# LEDBoard.net
KiCad netlist of a schematic drawn in EAGLE
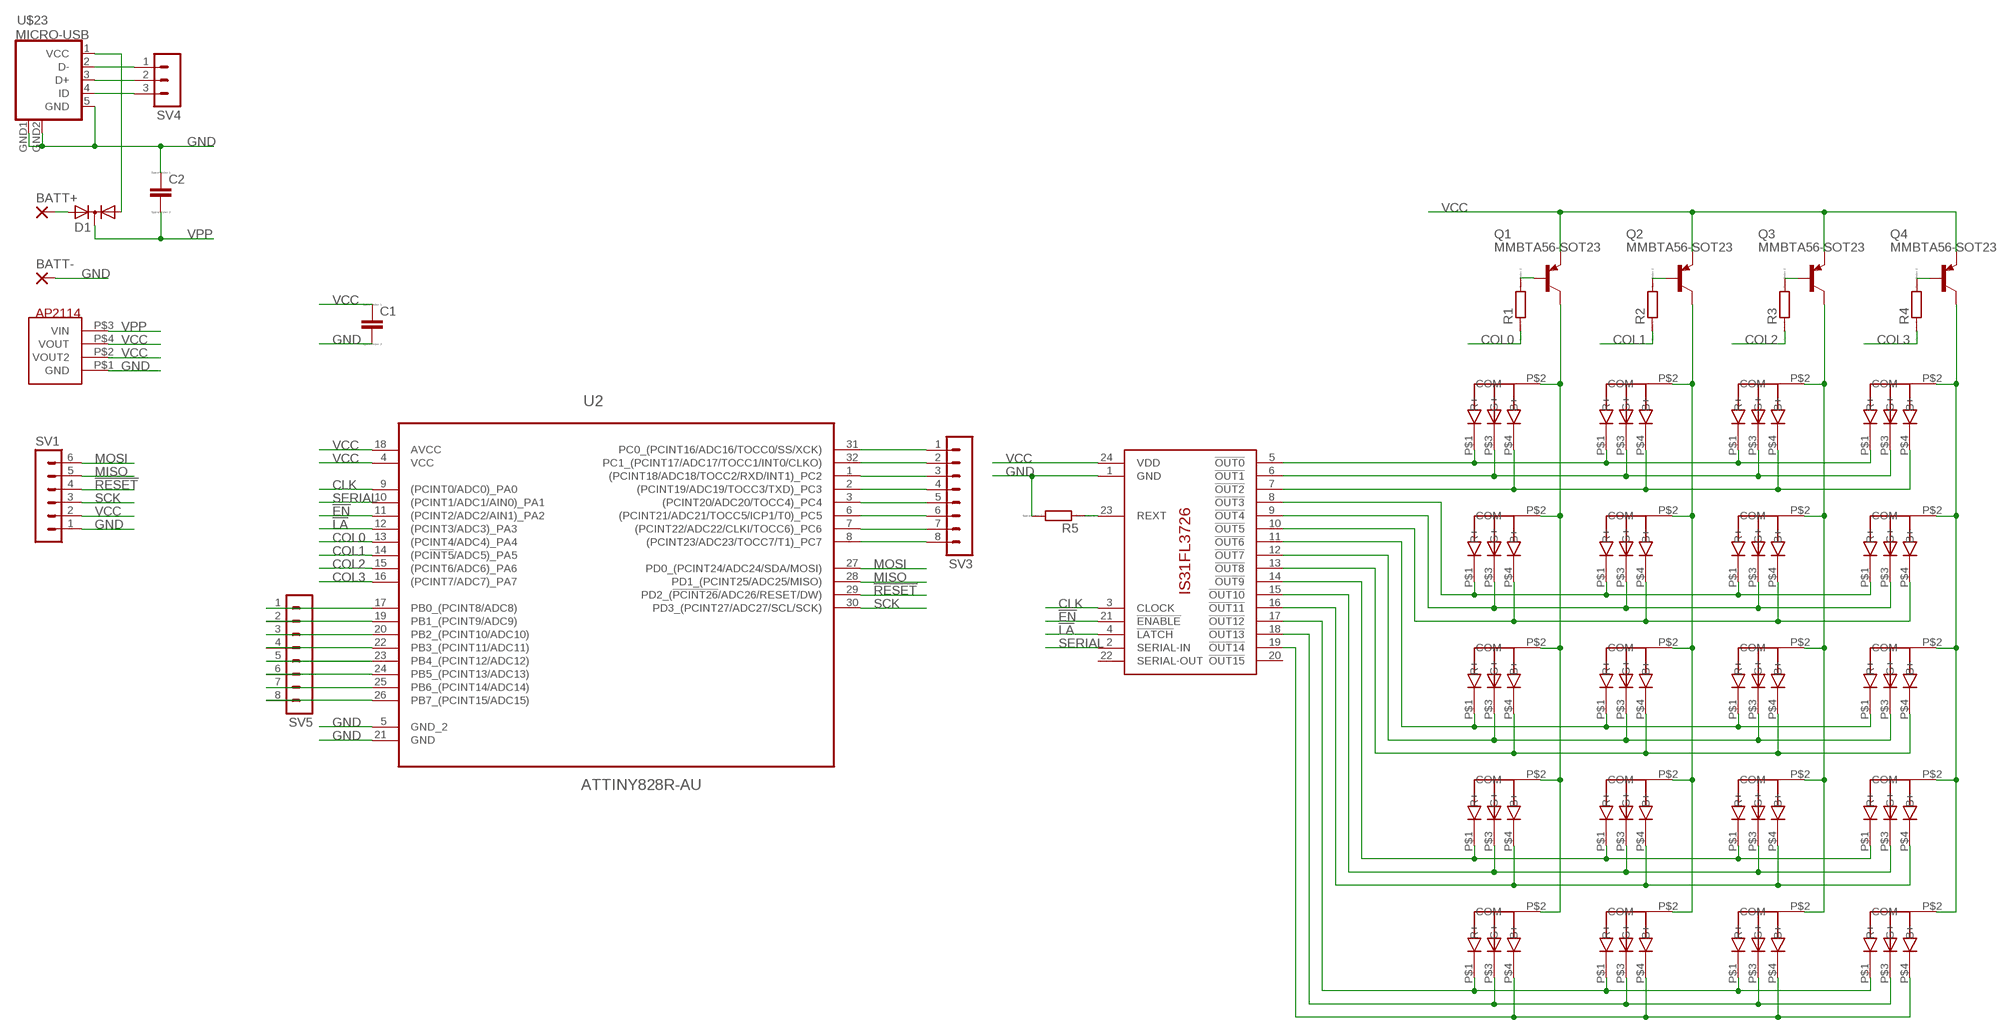
[diagram p0: schematic, sheet 1]

(export (version "E")
  (design (tool "Eeschema 10.0.6"))
  (components
    (comp (ref "BATT+")
      (value "2,54/1,1")
      (footprint "eagle-import:2,54_1,1")
      (libsource (lib "eagle-import") (part "2,54/1,1"))
    )
    (comp (ref "BATT-")
      (value "2,54/1,1")
      (footprint "eagle-import:2,54_1,1")
      (libsource (lib "eagle-import") (part "2,54/1,1"))
    )
    (comp (ref "C1")
      (value "CC1206")
      (footprint "eagle-import:C1206")
      (libsource (lib "eagle-import") (part "CC1206"))
    )
    (comp (ref "C2")
      (value "CC1206")
      (footprint "eagle-import:C1206")
      (libsource (lib "eagle-import") (part "CC1206"))
    )
    (comp (ref "D1")
      (value "DIODE-2AC|CASOT23")
      (footprint "eagle-import:SOT23")
      (libsource (lib "eagle-import") (part "DIODE-2AC|CASOT23"))
    )
    (comp (ref "Q1")
      (value "MMBTA56-SOT23")
      (footprint "eagle-import:SOT23")
      (libsource (lib "eagle-import") (part "-?SOT23MMBTA56"))
    )
    (comp (ref "Q2")
      (value "MMBTA56-SOT23")
      (footprint "eagle-import:SOT23")
      (libsource (lib "eagle-import") (part "-?SOT23MMBTA56"))
    )
    (comp (ref "Q3")
      (value "MMBTA56-SOT23")
      (footprint "eagle-import:SOT23")
      (libsource (lib "eagle-import") (part "-?SOT23MMBTA56"))
    )
    (comp (ref "Q4")
      (value "MMBTA56-SOT23")
      (footprint "eagle-import:SOT23")
      (libsource (lib "eagle-import") (part "-?SOT23MMBTA56"))
    )
    (comp (ref "R1")
      (value "RR1206")
      (footprint "eagle-import:R1206")
      (libsource (lib "eagle-import") (part "RR1206"))
    )
    (comp (ref "R2")
      (value "RR1206")
      (footprint "eagle-import:R1206")
      (libsource (lib "eagle-import") (part "RR1206"))
    )
    (comp (ref "R3")
      (value "RR1206")
      (footprint "eagle-import:R1206")
      (libsource (lib "eagle-import") (part "RR1206"))
    )
    (comp (ref "R4")
      (value "RR1206")
      (footprint "eagle-import:R1206")
      (libsource (lib "eagle-import") (part "RR1206"))
    )
    (comp (ref "R5")
      (value "RR1206")
      (footprint "eagle-import:R1206")
      (libsource (lib "eagle-import") (part "RR1206"))
    )
    (comp (ref "SV1")
      (value "MA06-1")
      (footprint "eagle-import:MA06-1")
      (libsource (lib "eagle-import") (part "MA06-1"))
    )
    (comp (ref "SV3")
      (value "MA08-1")
      (footprint "eagle-import:MA08-1")
      (libsource (lib "eagle-import") (part "MA08-1"))
    )
    (comp (ref "SV4")
      (value "MA03-1")
      (footprint "eagle-import:MA03-1")
      (libsource (lib "eagle-import") (part "MA03-1"))
    )
    (comp (ref "SV5")
      (value "MA08-1")
      (footprint "eagle-import:MA08-1")
      (libsource (lib "eagle-import") (part "MA08-1"))
    )
    (comp (ref "U$1")
      (value "IS31FL3726")
      (footprint "eagle-import:TSSOP-24")
      (libsource (lib "eagle-import") (part "IS31FL3726"))
    )
    (comp (ref "U$2")
      (value "AP2114H")
      (footprint "eagle-import:SOT233")
      (libsource (lib "eagle-import") (part "AP2114H"))
    )
    (comp (ref "U$3")
      (value "3528LED")
      (footprint "eagle-import:3528")
      (libsource (lib "eagle-import") (part "3528LED"))
    )
    (comp (ref "U$4")
      (value "3528LED")
      (footprint "eagle-import:3528")
      (libsource (lib "eagle-import") (part "3528LED"))
    )
    (comp (ref "U$5")
      (value "3528LED")
      (footprint "eagle-import:3528")
      (libsource (lib "eagle-import") (part "3528LED"))
    )
    (comp (ref "U$6")
      (value "3528LED")
      (footprint "eagle-import:3528")
      (libsource (lib "eagle-import") (part "3528LED"))
    )
    (comp (ref "U$7")
      (value "3528LED")
      (footprint "eagle-import:3528")
      (libsource (lib "eagle-import") (part "3528LED"))
    )
    (comp (ref "U$8")
      (value "3528LED")
      (footprint "eagle-import:3528")
      (libsource (lib "eagle-import") (part "3528LED"))
    )
    (comp (ref "U$9")
      (value "3528LED")
      (footprint "eagle-import:3528")
      (libsource (lib "eagle-import") (part "3528LED"))
    )
    (comp (ref "U$10")
      (value "3528LED")
      (footprint "eagle-import:3528")
      (libsource (lib "eagle-import") (part "3528LED"))
    )
    (comp (ref "U$11")
      (value "3528LED")
      (footprint "eagle-import:3528")
      (libsource (lib "eagle-import") (part "3528LED"))
    )
    (comp (ref "U$12")
      (value "3528LED")
      (footprint "eagle-import:3528")
      (libsource (lib "eagle-import") (part "3528LED"))
    )
    (comp (ref "U$13")
      (value "3528LED")
      (footprint "eagle-import:3528")
      (libsource (lib "eagle-import") (part "3528LED"))
    )
    (comp (ref "U$14")
      (value "3528LED")
      (footprint "eagle-import:3528")
      (libsource (lib "eagle-import") (part "3528LED"))
    )
    (comp (ref "U$15")
      (value "3528LED")
      (footprint "eagle-import:3528")
      (libsource (lib "eagle-import") (part "3528LED"))
    )
    (comp (ref "U$16")
      (value "3528LED")
      (footprint "eagle-import:3528")
      (libsource (lib "eagle-import") (part "3528LED"))
    )
    (comp (ref "U$17")
      (value "3528LED")
      (footprint "eagle-import:3528")
      (libsource (lib "eagle-import") (part "3528LED"))
    )
    (comp (ref "U$18")
      (value "3528LED")
      (footprint "eagle-import:3528")
      (libsource (lib "eagle-import") (part "3528LED"))
    )
    (comp (ref "U$19")
      (value "3528LED")
      (footprint "eagle-import:3528")
      (libsource (lib "eagle-import") (part "3528LED"))
    )
    (comp (ref "U$20")
      (value "3528LED")
      (footprint "eagle-import:3528")
      (libsource (lib "eagle-import") (part "3528LED"))
    )
    (comp (ref "U$21")
      (value "3528LED")
      (footprint "eagle-import:3528")
      (libsource (lib "eagle-import") (part "3528LED"))
    )
    (comp (ref "U$22")
      (value "3528LED")
      (footprint "eagle-import:3528")
      (libsource (lib "eagle-import") (part "3528LED"))
    )
    (comp (ref "U$23")
      (value "MICRO-USB")
      (footprint "eagle-import:MICRO-USB")
      (libsource (lib "eagle-import") (part "MICRO-USB"))
    )
    (comp (ref "U2")
      (value "ATTINY828R-AU")
      (footprint "eagle-import:QFP80P900X900X120-32N")
      (libsource (lib "eagle-import") (part "ATTINY828R-AU"))
    )
  )
  (nets
    (net (code "1") (name "/CLK") (class "Default")
      (node (ref "U$1") (pin "3") (pinfunction "CLOCK_3") (pintype "bidirectional"))
      (node (ref "U2") (pin "9") (pinfunction "(PCINT0/ADC0)_PA0_9") (pintype "bidirectional"))
    )
    (net (code "2") (name "/COL0") (class "Default")
      (node (ref "R1") (pin "1") (pinfunction "1_1") (pintype "passive"))
      (node (ref "U2") (pin "13") (pinfunction "(PCINT4/ADC4)_PA4_13") (pintype "bidirectional"))
    )
    (net (code "3") (name "/COL1") (class "Default")
      (node (ref "R2") (pin "1") (pinfunction "1_1") (pintype "passive"))
      (node (ref "U2") (pin "14") (pinfunction "(PC~{INT5}/ADC5)_PA5_14") (pintype "bidirectional"))
    )
    (net (code "4") (name "/COL2") (class "Default")
      (node (ref "R3") (pin "1") (pinfunction "1_1") (pintype "passive"))
      (node (ref "U2") (pin "15") (pinfunction "(PCINT6/ADC6)_PA6_15") (pintype "bidirectional"))
    )
    (net (code "5") (name "/COL3") (class "Default")
      (node (ref "R4") (pin "1") (pinfunction "1_1") (pintype "passive"))
      (node (ref "U2") (pin "16") (pinfunction "(PCINT7/ADC7)_PA7_16") (pintype "bidirectional"))
    )
    (net (code "6") (name "/GND") (class "Default")
      (node (ref "BATT-") (pin "1") (pinfunction "P_1") (pintype "passive"))
      (node (ref "C1") (pin "2") (pinfunction "2_2") (pintype "passive"))
      (node (ref "C2") (pin "1") (pinfunction "1_1") (pintype "passive"))
      (node (ref "R5") (pin "2") (pinfunction "2_2") (pintype "passive"))
      (node (ref "SV1") (pin "1") (pinfunction "1_1") (pintype "passive"))
      (node (ref "U$1") (pin "1") (pinfunction "GND_1") (pintype "bidirectional"))
      (node (ref "U$2") (pin "P$1") (pinfunction "GND_P$1") (pintype "bidirectional"))
      (node (ref "U$23") (pin "5") (pinfunction "GND_5") (pintype "power_in"))
      (node (ref "U$23") (pin "GND1") (pinfunction "GND_GND1") (pintype "power_in"))
      (node (ref "U$23") (pin "GND2") (pinfunction "GND_GND2") (pintype "power_in"))
      (node (ref "U2") (pin "21") (pinfunction "GND_21") (pintype "passive"))
      (node (ref "U2") (pin "5") (pinfunction "GND_2_5") (pintype "passive"))
    )
    (net (code "7") (name "/MISO") (class "Default")
      (node (ref "SV1") (pin "5") (pinfunction "5_5") (pintype "passive"))
      (node (ref "U2") (pin "28") (pinfunction "PD1_(PCINT25/ADC25/MISO)_28") (pintype "bidirectional"))
    )
    (net (code "8") (name "/MOSI") (class "Default")
      (node (ref "SV1") (pin "6") (pinfunction "6_6") (pintype "passive"))
      (node (ref "U2") (pin "27") (pinfunction "PD0_(PCINT24/ADC24/SDA/MOSI)_27") (pintype "bidirectional"))
    )
    (net (code "9") (name "/SCK") (class "Default")
      (node (ref "SV1") (pin "3") (pinfunction "3_3") (pintype "passive"))
      (node (ref "U2") (pin "30") (pinfunction "PD3_(PCINT27/ADC27/SCL/SCK)_30") (pintype "bidirectional"))
    )
    (net (code "10") (name "/SERIAL") (class "Default")
      (node (ref "U$1") (pin "2") (pinfunction "SERIAL-IN_2") (pintype "bidirectional"))
      (node (ref "U2") (pin "10") (pinfunction "(PCINT1/ADC1/AIN0)_PA1_10") (pintype "bidirectional"))
    )
    (net (code "11") (name "/VCC") (class "Default")
      (node (ref "C1") (pin "1") (pinfunction "1_1") (pintype "passive"))
      (node (ref "Q1") (pin "2") (pinfunction "E_2") (pintype "passive"))
      (node (ref "Q2") (pin "2") (pinfunction "E_2") (pintype "passive"))
      (node (ref "Q3") (pin "2") (pinfunction "E_2") (pintype "passive"))
      (node (ref "Q4") (pin "2") (pinfunction "E_2") (pintype "passive"))
      (node (ref "SV1") (pin "2") (pinfunction "2_2") (pintype "passive"))
      (node (ref "U$1") (pin "24") (pinfunction "VDD_24") (pintype "bidirectional"))
      (node (ref "U$2") (pin "P$2") (pinfunction "VOUT2_P$2") (pintype "bidirectional"))
      (node (ref "U$2") (pin "P$4") (pinfunction "VOUT_P$4") (pintype "bidirectional"))
      (node (ref "U2") (pin "18") (pinfunction "AVCC_18") (pintype "power_in"))
      (node (ref "U2") (pin "4") (pinfunction "VCC_4") (pintype "power_in"))
    )
    (net (code "12") (name "/VPP") (class "Default")
      (node (ref "C2") (pin "2") (pinfunction "2_2") (pintype "passive"))
      (node (ref "D1") (pin "3") (pinfunction "C_3") (pintype "passive"))
      (node (ref "U$2") (pin "P$3") (pinfunction "VIN_P$3") (pintype "bidirectional"))
    )
    (net (code "13") (name "/~{EN}") (class "Default")
      (node (ref "U$1") (pin "21") (pinfunction "~{ENABLE}_21") (pintype "bidirectional"))
      (node (ref "U2") (pin "11") (pinfunction "(PCINT2/ADC2/AIN1)_PA2_11") (pintype "bidirectional"))
    )
    (net (code "14") (name "/~{LA}") (class "Default")
      (node (ref "U$1") (pin "4") (pinfunction "~{LATCH}_4") (pintype "bidirectional"))
      (node (ref "U2") (pin "12") (pinfunction "(PCINT3/ADC3)_PA3_12") (pintype "bidirectional"))
    )
    (net (code "15") (name "/~{RESET}") (class "Default")
      (node (ref "SV1") (pin "4") (pinfunction "4_4") (pintype "passive"))
      (node (ref "U2") (pin "29") (pinfunction "PD2_(~{PCINT26}/ADC26/RESET/DW)_29") (pintype "bidirectional"))
    )
    (net (code "16") (name "Net-(BATT+-P)") (class "Default")
      (node (ref "BATT+") (pin "1") (pinfunction "P_1") (pintype "passive"))
      (node (ref "D1") (pin "2") (pinfunction "A2_2") (pintype "passive"))
    )
    (net (code "17") (name "Net-(D1-A1)") (class "Default")
      (node (ref "D1") (pin "1") (pinfunction "A1_1") (pintype "passive"))
      (node (ref "U$23") (pin "1") (pinfunction "VCC_1") (pintype "power_in"))
    )
    (net (code "18") (name "Net-(Q1-B)") (class "Default")
      (node (ref "Q1") (pin "1") (pinfunction "B_1") (pintype "passive"))
      (node (ref "R1") (pin "2") (pinfunction "2_2") (pintype "passive"))
    )
    (net (code "19") (name "Net-(Q1-C)") (class "Default")
      (node (ref "Q1") (pin "3") (pinfunction "C_3") (pintype "passive"))
      (node (ref "U$11") (pin "P$2") (pinfunction "COM_P$2") (pintype "bidirectional"))
      (node (ref "U$15") (pin "P$2") (pinfunction "COM_P$2") (pintype "bidirectional"))
      (node (ref "U$22") (pin "P$2") (pinfunction "COM_P$2") (pintype "bidirectional"))
      (node (ref "U$3") (pin "P$2") (pinfunction "COM_P$2") (pintype "bidirectional"))
      (node (ref "U$7") (pin "P$2") (pinfunction "COM_P$2") (pintype "bidirectional"))
    )
    (net (code "20") (name "Net-(Q2-B)") (class "Default")
      (node (ref "Q2") (pin "1") (pinfunction "B_1") (pintype "passive"))
      (node (ref "R2") (pin "2") (pinfunction "2_2") (pintype "passive"))
    )
    (net (code "21") (name "Net-(Q2-C)") (class "Default")
      (node (ref "Q2") (pin "3") (pinfunction "C_3") (pintype "passive"))
      (node (ref "U$12") (pin "P$2") (pinfunction "COM_P$2") (pintype "bidirectional"))
      (node (ref "U$16") (pin "P$2") (pinfunction "COM_P$2") (pintype "bidirectional"))
      (node (ref "U$21") (pin "P$2") (pinfunction "COM_P$2") (pintype "bidirectional"))
      (node (ref "U$4") (pin "P$2") (pinfunction "COM_P$2") (pintype "bidirectional"))
      (node (ref "U$8") (pin "P$2") (pinfunction "COM_P$2") (pintype "bidirectional"))
    )
    (net (code "22") (name "Net-(Q3-B)") (class "Default")
      (node (ref "Q3") (pin "1") (pinfunction "B_1") (pintype "passive"))
      (node (ref "R3") (pin "2") (pinfunction "2_2") (pintype "passive"))
    )
    (net (code "23") (name "Net-(Q3-C)") (class "Default")
      (node (ref "Q3") (pin "3") (pinfunction "C_3") (pintype "passive"))
      (node (ref "U$13") (pin "P$2") (pinfunction "COM_P$2") (pintype "bidirectional"))
      (node (ref "U$17") (pin "P$2") (pinfunction "COM_P$2") (pintype "bidirectional"))
      (node (ref "U$20") (pin "P$2") (pinfunction "COM_P$2") (pintype "bidirectional"))
      (node (ref "U$5") (pin "P$2") (pinfunction "COM_P$2") (pintype "bidirectional"))
      (node (ref "U$9") (pin "P$2") (pinfunction "COM_P$2") (pintype "bidirectional"))
    )
    (net (code "24") (name "Net-(Q4-B)") (class "Default")
      (node (ref "Q4") (pin "1") (pinfunction "B_1") (pintype "passive"))
      (node (ref "R4") (pin "2") (pinfunction "2_2") (pintype "passive"))
    )
    (net (code "25") (name "Net-(Q4-C)") (class "Default")
      (node (ref "Q4") (pin "3") (pinfunction "C_3") (pintype "passive"))
      (node (ref "U$10") (pin "P$2") (pinfunction "COM_P$2") (pintype "bidirectional"))
      (node (ref "U$14") (pin "P$2") (pinfunction "COM_P$2") (pintype "bidirectional"))
      (node (ref "U$18") (pin "P$2") (pinfunction "COM_P$2") (pintype "bidirectional"))
      (node (ref "U$19") (pin "P$2") (pinfunction "COM_P$2") (pintype "bidirectional"))
      (node (ref "U$6") (pin "P$2") (pinfunction "COM_P$2") (pintype "bidirectional"))
    )
    (net (code "26") (name "Net-(U$1-REXT)") (class "Default")
      (node (ref "R5") (pin "1") (pinfunction "1_1") (pintype "passive"))
      (node (ref "U$1") (pin "23") (pinfunction "REXT_23") (pintype "bidirectional"))
    )
    (net (code "27") (name "Net-(U$1-~{OUT0})") (class "Default")
      (node (ref "U$1") (pin "5") (pinfunction "~{OUT0}_5") (pintype "bidirectional"))
      (node (ref "U$10") (pin "P$1") (pinfunction "R+_P$1") (pintype "bidirectional"))
      (node (ref "U$7") (pin "P$1") (pinfunction "R+_P$1") (pintype "bidirectional"))
      (node (ref "U$8") (pin "P$1") (pinfunction "R+_P$1") (pintype "bidirectional"))
      (node (ref "U$9") (pin "P$1") (pinfunction "R+_P$1") (pintype "bidirectional"))
    )
    (net (code "28") (name "Net-(U$1-~{OUT1})") (class "Default")
      (node (ref "U$1") (pin "6") (pinfunction "~{OUT1}_6") (pintype "bidirectional"))
      (node (ref "U$10") (pin "P$3") (pinfunction "G+_P$3") (pintype "bidirectional"))
      (node (ref "U$7") (pin "P$3") (pinfunction "G+_P$3") (pintype "bidirectional"))
      (node (ref "U$8") (pin "P$3") (pinfunction "G+_P$3") (pintype "bidirectional"))
      (node (ref "U$9") (pin "P$3") (pinfunction "G+_P$3") (pintype "bidirectional"))
    )
    (net (code "29") (name "Net-(U$1-~{OUT2})") (class "Default")
      (node (ref "U$1") (pin "7") (pinfunction "~{OUT2}_7") (pintype "bidirectional"))
      (node (ref "U$10") (pin "P$4") (pinfunction "B+_P$4") (pintype "bidirectional"))
      (node (ref "U$7") (pin "P$4") (pinfunction "B+_P$4") (pintype "bidirectional"))
      (node (ref "U$8") (pin "P$4") (pinfunction "B+_P$4") (pintype "bidirectional"))
      (node (ref "U$9") (pin "P$4") (pinfunction "B+_P$4") (pintype "bidirectional"))
    )
    (net (code "30") (name "Net-(U$1-~{OUT3})") (class "Default")
      (node (ref "U$1") (pin "8") (pinfunction "~{OUT3}_8") (pintype "bidirectional"))
      (node (ref "U$3") (pin "P$1") (pinfunction "R+_P$1") (pintype "bidirectional"))
      (node (ref "U$4") (pin "P$1") (pinfunction "R+_P$1") (pintype "bidirectional"))
      (node (ref "U$5") (pin "P$1") (pinfunction "R+_P$1") (pintype "bidirectional"))
      (node (ref "U$6") (pin "P$1") (pinfunction "R+_P$1") (pintype "bidirectional"))
    )
    (net (code "31") (name "Net-(U$1-~{OUT4})") (class "Default")
      (node (ref "U$1") (pin "9") (pinfunction "~{OUT4}_9") (pintype "bidirectional"))
      (node (ref "U$3") (pin "P$3") (pinfunction "G+_P$3") (pintype "bidirectional"))
      (node (ref "U$4") (pin "P$3") (pinfunction "G+_P$3") (pintype "bidirectional"))
      (node (ref "U$5") (pin "P$3") (pinfunction "G+_P$3") (pintype "bidirectional"))
      (node (ref "U$6") (pin "P$3") (pinfunction "G+_P$3") (pintype "bidirectional"))
    )
    (net (code "32") (name "Net-(U$1-~{OUT5})") (class "Default")
      (node (ref "U$1") (pin "10") (pinfunction "~{OUT5}_10") (pintype "bidirectional"))
      (node (ref "U$3") (pin "P$4") (pinfunction "B+_P$4") (pintype "bidirectional"))
      (node (ref "U$4") (pin "P$4") (pinfunction "B+_P$4") (pintype "bidirectional"))
      (node (ref "U$5") (pin "P$4") (pinfunction "B+_P$4") (pintype "bidirectional"))
      (node (ref "U$6") (pin "P$4") (pinfunction "B+_P$4") (pintype "bidirectional"))
    )
    (net (code "33") (name "Net-(U$1-~{OUT6})") (class "Default")
      (node (ref "U$1") (pin "11") (pinfunction "~{OUT6}_11") (pintype "bidirectional"))
      (node (ref "U$11") (pin "P$1") (pinfunction "R+_P$1") (pintype "bidirectional"))
      (node (ref "U$12") (pin "P$1") (pinfunction "R+_P$1") (pintype "bidirectional"))
      (node (ref "U$13") (pin "P$1") (pinfunction "R+_P$1") (pintype "bidirectional"))
      (node (ref "U$14") (pin "P$1") (pinfunction "R+_P$1") (pintype "bidirectional"))
    )
    (net (code "34") (name "Net-(U$1-~{OUT7})") (class "Default")
      (node (ref "U$1") (pin "12") (pinfunction "~{OUT7}_12") (pintype "bidirectional"))
      (node (ref "U$11") (pin "P$3") (pinfunction "G+_P$3") (pintype "bidirectional"))
      (node (ref "U$12") (pin "P$3") (pinfunction "G+_P$3") (pintype "bidirectional"))
      (node (ref "U$13") (pin "P$3") (pinfunction "G+_P$3") (pintype "bidirectional"))
      (node (ref "U$14") (pin "P$3") (pinfunction "G+_P$3") (pintype "bidirectional"))
    )
    (net (code "35") (name "Net-(U$1-~{OUT8})") (class "Default")
      (node (ref "U$1") (pin "13") (pinfunction "~{OUT8}_13") (pintype "bidirectional"))
      (node (ref "U$11") (pin "P$4") (pinfunction "B+_P$4") (pintype "bidirectional"))
      (node (ref "U$12") (pin "P$4") (pinfunction "B+_P$4") (pintype "bidirectional"))
      (node (ref "U$13") (pin "P$4") (pinfunction "B+_P$4") (pintype "bidirectional"))
      (node (ref "U$14") (pin "P$4") (pinfunction "B+_P$4") (pintype "bidirectional"))
    )
    (net (code "36") (name "Net-(U$1-~{OUT9})") (class "Default")
      (node (ref "U$1") (pin "14") (pinfunction "~{OUT9}_14") (pintype "bidirectional"))
      (node (ref "U$15") (pin "P$1") (pinfunction "R+_P$1") (pintype "bidirectional"))
      (node (ref "U$16") (pin "P$1") (pinfunction "R+_P$1") (pintype "bidirectional"))
      (node (ref "U$17") (pin "P$1") (pinfunction "R+_P$1") (pintype "bidirectional"))
      (node (ref "U$18") (pin "P$1") (pinfunction "R+_P$1") (pintype "bidirectional"))
    )
    (net (code "37") (name "Net-(U$1-~{OUT10})") (class "Default")
      (node (ref "U$1") (pin "15") (pinfunction "~{OUT10}_15") (pintype "bidirectional"))
      (node (ref "U$15") (pin "P$3") (pinfunction "G+_P$3") (pintype "bidirectional"))
      (node (ref "U$16") (pin "P$3") (pinfunction "G+_P$3") (pintype "bidirectional"))
      (node (ref "U$17") (pin "P$3") (pinfunction "G+_P$3") (pintype "bidirectional"))
      (node (ref "U$18") (pin "P$3") (pinfunction "G+_P$3") (pintype "bidirectional"))
    )
    (net (code "38") (name "Net-(U$1-~{OUT11})") (class "Default")
      (node (ref "U$1") (pin "16") (pinfunction "~{OUT11}_16") (pintype "bidirectional"))
      (node (ref "U$15") (pin "P$4") (pinfunction "B+_P$4") (pintype "bidirectional"))
      (node (ref "U$16") (pin "P$4") (pinfunction "B+_P$4") (pintype "bidirectional"))
      (node (ref "U$17") (pin "P$4") (pinfunction "B+_P$4") (pintype "bidirectional"))
      (node (ref "U$18") (pin "P$4") (pinfunction "B+_P$4") (pintype "bidirectional"))
    )
    (net (code "39") (name "Net-(U$1-~{OUT12})") (class "Default")
      (node (ref "U$1") (pin "17") (pinfunction "~{OUT12}_17") (pintype "bidirectional"))
      (node (ref "U$19") (pin "P$1") (pinfunction "R+_P$1") (pintype "bidirectional"))
      (node (ref "U$20") (pin "P$1") (pinfunction "R+_P$1") (pintype "bidirectional"))
      (node (ref "U$21") (pin "P$1") (pinfunction "R+_P$1") (pintype "bidirectional"))
      (node (ref "U$22") (pin "P$1") (pinfunction "R+_P$1") (pintype "bidirectional"))
    )
    (net (code "40") (name "Net-(U$1-~{OUT13})") (class "Default")
      (node (ref "U$1") (pin "18") (pinfunction "~{OUT13}_18") (pintype "bidirectional"))
      (node (ref "U$19") (pin "P$3") (pinfunction "G+_P$3") (pintype "bidirectional"))
      (node (ref "U$20") (pin "P$3") (pinfunction "G+_P$3") (pintype "bidirectional"))
      (node (ref "U$21") (pin "P$3") (pinfunction "G+_P$3") (pintype "bidirectional"))
      (node (ref "U$22") (pin "P$3") (pinfunction "G+_P$3") (pintype "bidirectional"))
    )
    (net (code "41") (name "Net-(U$1-~{OUT14})") (class "Default")
      (node (ref "U$1") (pin "19") (pinfunction "~{OUT14}_19") (pintype "bidirectional"))
      (node (ref "U$19") (pin "P$4") (pinfunction "B+_P$4") (pintype "bidirectional"))
      (node (ref "U$20") (pin "P$4") (pinfunction "B+_P$4") (pintype "bidirectional"))
      (node (ref "U$21") (pin "P$4") (pinfunction "B+_P$4") (pintype "bidirectional"))
      (node (ref "U$22") (pin "P$4") (pinfunction "B+_P$4") (pintype "bidirectional"))
    )
    (net (code "42") (name "Net-(U$23-D+)") (class "Default")
      (node (ref "SV4") (pin "2") (pinfunction "2_2") (pintype "passive"))
      (node (ref "U$23") (pin "3") (pinfunction "D+_3") (pintype "bidirectional"))
    )
    (net (code "43") (name "Net-(U$23-D-)") (class "Default")
      (node (ref "SV4") (pin "1") (pinfunction "1_1") (pintype "passive"))
      (node (ref "U$23") (pin "2") (pinfunction "D-_2") (pintype "bidirectional"))
    )
    (net (code "44") (name "Net-(U$23-ID)") (class "Default")
      (node (ref "SV4") (pin "3") (pinfunction "3_3") (pintype "passive"))
      (node (ref "U$23") (pin "4") (pinfunction "ID_4") (pintype "bidirectional"))
    )
    (net (code "45") (name "Net-(U2-(PCINT18{slash}ADC18{slash}TOCC2{slash}RXD{slash}INT1)_PC2)") (class "Default")
      (node (ref "SV3") (pin "3") (pinfunction "3_3") (pintype "passive"))
      (node (ref "U2") (pin "1") (pinfunction "(PCINT18/ADC18/TOCC2/RXD/INT1)_PC2_1") (pintype "bidirectional"))
    )
    (net (code "46") (name "Net-(U2-(PCINT19{slash}ADC19{slash}TOCC3{slash}TXD)_PC3)") (class "Default")
      (node (ref "SV3") (pin "4") (pinfunction "4_4") (pintype "passive"))
      (node (ref "U2") (pin "2") (pinfunction "(PCINT19/ADC19/TOCC3/TXD)_PC3_2") (pintype "bidirectional"))
    )
    (net (code "47") (name "Net-(U2-(PCINT20{slash}ADC20{slash}TOCC4)_PC4)") (class "Default")
      (node (ref "SV3") (pin "5") (pinfunction "5_5") (pintype "passive"))
      (node (ref "U2") (pin "3") (pinfunction "(PCINT20/ADC20/TOCC4)_PC4_3") (pintype "bidirectional"))
    )
    (net (code "48") (name "Net-(U2-(PCINT21{slash}ADC21{slash}TOCC5{slash}ICP1{slash}T0)_PC5)") (class "Default")
      (node (ref "SV3") (pin "6") (pinfunction "6_6") (pintype "passive"))
      (node (ref "U2") (pin "6") (pinfunction "(PCINT21/ADC21/TOCC5/ICP1/T0)_PC5_6") (pintype "bidirectional"))
    )
    (net (code "49") (name "Net-(U2-(PCINT22{slash}ADC22{slash}CLKI{slash}TOCC6)_PC6)") (class "Default")
      (node (ref "SV3") (pin "7") (pinfunction "7_7") (pintype "passive"))
      (node (ref "U2") (pin "7") (pinfunction "(PCINT22/ADC22/CLKI/TOCC6)_PC6_7") (pintype "bidirectional"))
    )
    (net (code "50") (name "Net-(U2-(PCINT23{slash}ADC23{slash}TOCC7{slash}T1)_PC7)") (class "Default")
      (node (ref "SV3") (pin "8") (pinfunction "8_8") (pintype "passive"))
      (node (ref "U2") (pin "8") (pinfunction "(PCINT23/ADC23/TOCC7/T1)_PC7_8") (pintype "bidirectional"))
    )
    (net (code "51") (name "Net-(U2-PB0_(PCINT8{slash}ADC8))") (class "Default")
      (node (ref "SV5") (pin "1") (pinfunction "1_1") (pintype "passive"))
      (node (ref "U2") (pin "17") (pinfunction "PB0_(PCINT8/ADC8)_17") (pintype "bidirectional"))
    )
    (net (code "52") (name "Net-(U2-PB1_(PCINT9{slash}ADC9))") (class "Default")
      (node (ref "SV5") (pin "2") (pinfunction "2_2") (pintype "passive"))
      (node (ref "U2") (pin "19") (pinfunction "PB1_(PCINT9/ADC9)_19") (pintype "bidirectional"))
    )
    (net (code "53") (name "Net-(U2-PB2_(PCINT10{slash}ADC10))") (class "Default")
      (node (ref "SV5") (pin "3") (pinfunction "3_3") (pintype "passive"))
      (node (ref "U2") (pin "20") (pinfunction "PB2_(PCINT10/ADC10)_20") (pintype "bidirectional"))
    )
    (net (code "54") (name "Net-(U2-PB3_(PCINT11{slash}ADC11))") (class "Default")
      (node (ref "SV5") (pin "4") (pinfunction "4_4") (pintype "passive"))
      (node (ref "U2") (pin "22") (pinfunction "PB3_(PCINT11/ADC11)_22") (pintype "bidirectional"))
    )
    (net (code "55") (name "Net-(U2-PB4_(PCINT12{slash}ADC12))") (class "Default")
      (node (ref "SV5") (pin "5") (pinfunction "5_5") (pintype "passive"))
      (node (ref "U2") (pin "23") (pinfunction "PB4_(PCINT12/ADC12)_23") (pintype "bidirectional"))
    )
    (net (code "56") (name "Net-(U2-PB5_(PCINT13{slash}ADC13))") (class "Default")
      (node (ref "SV5") (pin "6") (pinfunction "6_6") (pintype "passive"))
      (node (ref "U2") (pin "24") (pinfunction "PB5_(PCINT13/ADC13)_24") (pintype "bidirectional"))
    )
    (net (code "57") (name "Net-(U2-PB6_(PCINT14{slash}ADC14))") (class "Default")
      (node (ref "SV5") (pin "7") (pinfunction "7_7") (pintype "passive"))
      (node (ref "U2") (pin "25") (pinfunction "PB6_(PCINT14/ADC14)_25") (pintype "bidirectional"))
    )
    (net (code "58") (name "Net-(U2-PB7_(PCINT15{slash}ADC15))") (class "Default")
      (node (ref "SV5") (pin "8") (pinfunction "8_8") (pintype "passive"))
      (node (ref "U2") (pin "26") (pinfunction "PB7_(PCINT15/ADC15)_26") (pintype "bidirectional"))
    )
    (net (code "59") (name "Net-(U2-PC0_(PCINT16{slash}ADC16{slash}TOCC0{slash}SS{slash}XCK))") (class "Default")
      (node (ref "SV3") (pin "1") (pinfunction "1_1") (pintype "passive"))
      (node (ref "U2") (pin "31") (pinfunction "PC0_(PCINT16/ADC16/TOCC0/SS/XCK)_31") (pintype "bidirectional"))
    )
    (net (code "60") (name "Net-(U2-PC1_(PCINT17{slash}ADC17{slash}TOCC1{slash}INT0{slash}CLKO))") (class "Default")
      (node (ref "SV3") (pin "2") (pinfunction "2_2") (pintype "passive"))
      (node (ref "U2") (pin "32") (pinfunction "PC1_(PCINT17/ADC17/TOCC1/INT0/CLKO)_32") (pintype "bidirectional"))
    )
    (net (code "61") (name "unconnected-(U$1-SERIAL-OUT-Pad22)") (class "Default")
      (node (ref "U$1") (pin "22") (pinfunction "SERIAL-OUT_22") (pintype "bidirectional"))
    )
    (net (code "62") (name "unconnected-(U$1-~{OUT15}-Pad20)") (class "Default")
      (node (ref "U$1") (pin "20") (pinfunction "~{OUT15}_20") (pintype "bidirectional"))
    )
  )
)
